# 1010829PA_HVFlyback_GD_Testboard_GDSuppl.net
KiCad netlist of a schematic drawn in Altium Designer
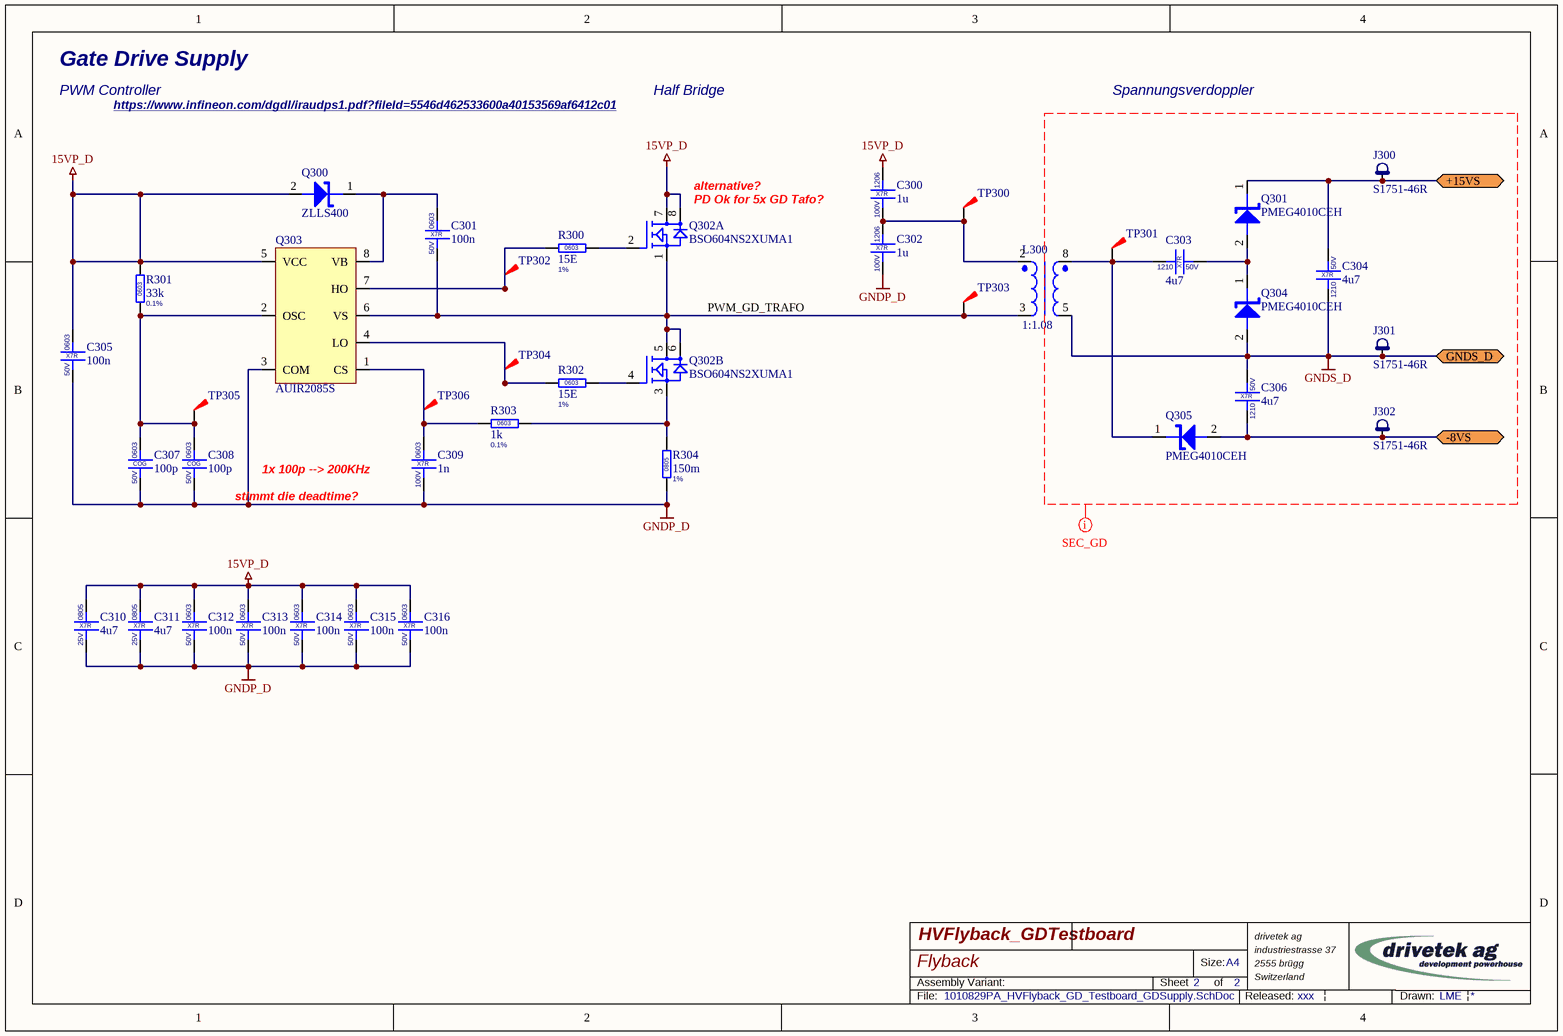
[diagram p0: 1010829PA_HVFlyback_GD_Testboard_GDSupply.SchDoc]

(export (version "E")
  (design (tool "Eeschema 10.0.6"))
  (components
    (comp (ref "C300")
      (value "1u")
      (footprint "02_1206_DRK_3-4x1-8x1-8")
      (fields
        (field (name "CASENAME") "1206")
        (field (name "TYPE3") "X7R")
        (field (name "VOLTAGE") "100V")
        (field (name "PART NUMBER") "02-0297")
        (field (name "TOLERANCE") "10")
        (field (name "AUTHOR") "CSI")
      )
      (libsource (lib "drivetek") (part "02_CAP"))
    )
    (comp (ref "C301")
      (value "100n")
      (footprint "02_0603_DRK_1-7x1-0x0-9")
      (fields
        (field (name "CASENAME") "0603")
        (field (name "TYPE3") "X7R")
        (field (name "VOLTAGE") "50V")
        (field (name "PART NUMBER") "02-0342")
        (field (name "TOLERANCE") "10")
        (field (name "AUTHOR") "RLE")
      )
      (libsource (lib "drivetek") (part "02_CAP"))
    )
    (comp (ref "C302")
      (value "1u")
      (footprint "02_1206_DRK_3-4x1-8x1-8")
      (fields
        (field (name "CASENAME") "1206")
        (field (name "TYPE3") "X7R")
        (field (name "VOLTAGE") "100V")
        (field (name "PART NUMBER") "02-0297")
        (field (name "TOLERANCE") "10")
        (field (name "AUTHOR") "CSI")
      )
      (libsource (lib "drivetek") (part "02_CAP"))
    )
    (comp (ref "C303")
      (value "4u7")
      (footprint "02_1210_DRK_3-2x2-6x2-7")
      (fields
        (field (name "CASENAME") "1210")
        (field (name "TYPE3") "X7R")
        (field (name "VOLTAGE") "50V")
        (field (name "PART NUMBER") "02-0107")
        (field (name "TOLERANCE") "10")
        (field (name "CHECKED") "SBR")
      )
      (libsource (lib "drivetek") (part "02_CAP"))
    )
    (comp (ref "C304")
      (value "4u7")
      (footprint "02_1210_DRK_3-2x2-6x2-7")
      (fields
        (field (name "CASENAME") "1210")
        (field (name "TYPE3") "X7R")
        (field (name "VOLTAGE") "50V")
        (field (name "PART NUMBER") "02-0107")
        (field (name "TOLERANCE") "10")
        (field (name "CHECKED") "SBR")
      )
      (libsource (lib "drivetek") (part "02_CAP"))
    )
    (comp (ref "C305")
      (value "100n")
      (footprint "02_0603_DRK_1-7x1-0x0-9")
      (fields
        (field (name "CASENAME") "0603")
        (field (name "TYPE3") "X7R")
        (field (name "VOLTAGE") "50V")
        (field (name "PART NUMBER") "02-0342")
        (field (name "TOLERANCE") "10")
        (field (name "AUTHOR") "RLE")
      )
      (libsource (lib "drivetek") (part "02_CAP"))
    )
    (comp (ref "C306")
      (value "4u7")
      (footprint "02_1210_DRK_3-2x2-6x2-7")
      (fields
        (field (name "CASENAME") "1210")
        (field (name "TYPE3") "X7R")
        (field (name "VOLTAGE") "50V")
        (field (name "PART NUMBER") "02-0107")
        (field (name "TOLERANCE") "10")
        (field (name "CHECKED") "SBR")
      )
      (libsource (lib "drivetek") (part "02_CAP"))
    )
    (comp (ref "C307")
      (value "100p")
      (footprint "02_0603_DRK_1-7x1-0x0-9")
      (fields
        (field (name "CASENAME") "0603")
        (field (name "TYPE3") "COG")
        (field (name "VOLTAGE") "50V")
        (field (name "PART NUMBER") "02-0380")
        (field (name "TOLERANCE") "5")
        (field (name "AUTHOR") "RLE")
      )
      (libsource (lib "drivetek") (part "02_CAP"))
    )
    (comp (ref "C308")
      (value "100p")
      (footprint "02_0603_DRK_1-7x1-0x0-9")
      (fields
        (field (name "CASENAME") "0603")
        (field (name "TYPE3") "COG")
        (field (name "VOLTAGE") "50V")
        (field (name "PART NUMBER") "02-0380")
        (field (name "TOLERANCE") "5")
        (field (name "AUTHOR") "RLE")
      )
      (libsource (lib "drivetek") (part "02_CAP"))
    )
    (comp (ref "C309")
      (value "1n")
      (footprint "02_0603_DRK_1-7x1-0x0-9")
      (fields
        (field (name "CASENAME") "0603")
        (field (name "TYPE3") "X7R")
        (field (name "VOLTAGE") "100V")
        (field (name "PART NUMBER") "02-0303")
        (field (name "TOLERANCE") "10")
        (field (name "AUTHOR") "RLE")
      )
      (libsource (lib "drivetek") (part "02_CAP"))
    )
    (comp (ref "C310")
      (value "4u7")
      (footprint "02_0805_DRK_2-2x1-5x1-3")
      (fields
        (field (name "CASENAME") "0805")
        (field (name "TYPE3") "X7R")
        (field (name "VOLTAGE") "25V")
        (field (name "PART NUMBER") "02-0268")
        (field (name "TOLERANCE") "10")
        (field (name "AUTHOR") "MFR")
      )
      (libsource (lib "drivetek") (part "02_CAP"))
    )
    (comp (ref "C311")
      (value "4u7")
      (footprint "02_0805_DRK_2-2x1-5x1-3")
      (fields
        (field (name "CASENAME") "0805")
        (field (name "TYPE3") "X7R")
        (field (name "VOLTAGE") "25V")
        (field (name "PART NUMBER") "02-0268")
        (field (name "TOLERANCE") "10")
        (field (name "AUTHOR") "MFR")
      )
      (libsource (lib "drivetek") (part "02_CAP"))
    )
    (comp (ref "C312")
      (value "100n")
      (footprint "02_0603_DRK_1-7x1-0x0-9")
      (fields
        (field (name "CASENAME") "0603")
        (field (name "TYPE3") "X7R")
        (field (name "VOLTAGE") "50V")
        (field (name "PART NUMBER") "02-0342")
        (field (name "TOLERANCE") "10")
        (field (name "AUTHOR") "RLE")
      )
      (libsource (lib "drivetek") (part "02_CAP"))
    )
    (comp (ref "C313")
      (value "100n")
      (footprint "02_0603_DRK_1-7x1-0x0-9")
      (fields
        (field (name "CASENAME") "0603")
        (field (name "TYPE3") "X7R")
        (field (name "VOLTAGE") "50V")
        (field (name "PART NUMBER") "02-0342")
        (field (name "TOLERANCE") "10")
        (field (name "AUTHOR") "RLE")
      )
      (libsource (lib "drivetek") (part "02_CAP"))
    )
    (comp (ref "C314")
      (value "100n")
      (footprint "02_0603_DRK_1-7x1-0x0-9")
      (fields
        (field (name "CASENAME") "0603")
        (field (name "TYPE3") "X7R")
        (field (name "VOLTAGE") "50V")
        (field (name "PART NUMBER") "02-0342")
        (field (name "TOLERANCE") "10")
        (field (name "AUTHOR") "RLE")
      )
      (libsource (lib "drivetek") (part "02_CAP"))
    )
    (comp (ref "C315")
      (value "100n")
      (footprint "02_0603_DRK_1-7x1-0x0-9")
      (fields
        (field (name "CASENAME") "0603")
        (field (name "TYPE3") "X7R")
        (field (name "VOLTAGE") "50V")
        (field (name "PART NUMBER") "02-0342")
        (field (name "TOLERANCE") "10")
        (field (name "AUTHOR") "RLE")
      )
      (libsource (lib "drivetek") (part "02_CAP"))
    )
    (comp (ref "C316")
      (value "100n")
      (footprint "02_0603_DRK_1-7x1-0x0-9")
      (fields
        (field (name "CASENAME") "0603")
        (field (name "TYPE3") "X7R")
        (field (name "VOLTAGE") "50V")
        (field (name "PART NUMBER") "02-0342")
        (field (name "TOLERANCE") "10")
        (field (name "AUTHOR") "RLE")
      )
      (libsource (lib "drivetek") (part "02_CAP"))
    )
    (comp (ref "J300")
      (value "S1751-46R")
      (footprint "13_PAD_DRK_HARWIN_S1751-46")
      (description "Probe Hook")
      (fields (field (name "PART NUMBER") "13-0487") (field (name "AUTHOR") "CSI"))
      (libsource (lib "drivetek") (part "13_ProbeHook"))
    )
    (comp (ref "J301")
      (value "S1751-46R")
      (footprint "13_PAD_DRK_HARWIN_S1751-46")
      (description "Probe Hook")
      (fields (field (name "PART NUMBER") "13-0487") (field (name "AUTHOR") "CSI"))
      (libsource (lib "drivetek") (part "13_ProbeHook"))
    )
    (comp (ref "J302")
      (value "S1751-46R")
      (footprint "13_PAD_DRK_HARWIN_S1751-46")
      (description "Probe Hook")
      (fields (field (name "PART NUMBER") "13-0487") (field (name "AUTHOR") "CSI"))
      (libsource (lib "drivetek") (part "13_ProbeHook"))
    )
    (comp (ref "L300")
      (value "1:1.08")
      (footprint "06_TRA_DRK_TDK-B78307A2276A003")
      (description "Gate Drive Transformer")
      (fields
        (field (name "PART NUMBER") "06-0146")
        (field (name "AUTHOR") "NLE")
        (field (name "COMPONENTLINK1URL") "K:\\Volkswagen\\1779_LE_BZ_Luftversorgung\\03_Hardware\\031_Analyse_Spezifikation\\BS1\\Datenblätter\\Gate Drive Supply\\B78307A2276A003.pdf")
      )
      (libsource (lib "drivetek") (part "06_TRA_DRK_TDK-B78307A2276A003"))
    )
    (comp (ref "Q300")
      (value "ZLLS400")
      (footprint "03_SOD323_DRK")
      (fields
        (field (name "PART NUMBER") "03-0389")
        (field (name "VOLTAGE") "40V")
        (field (name "AUTHOR") "RLE")
        (field (name "CHECKED") "CRA")
      )
      (libsource (lib "drivetek") (part "03_SCHOTTKY_A2-K1"))
    )
    (comp (ref "Q301")
      (value "PMEG4010CEH")
      (footprint "03_SOD123_DRK")
      (fields
        (field (name "PART NUMBER") "03-0124")
        (field (name "VOLTAGE") "40V")
        (field (name "AUTHOR") "MSC")
        (field (name "CHECKED") "HHU")
      )
      (libsource (lib "drivetek") (part "03_SCHOTTKY_A2-K1"))
    )
    (comp (ref "Q302")
      (value "BSO604NS2XUMA1")
      (footprint "03_SO-8_DRK")
      (description "OptiMOS Dual N-Channel 5A 55V 35mOhm, AEC-Q101")
      (fields
        (field (name "PART NUMBER") "03-0419")
        (field (name "VOLTAGE") "55V")
        (field (name "AUTHOR") "RVI")
      )
      (libsource (lib "drivetek") (part "03_NMOS_DUAL_BSO604NS2"))
    )
    (comp (ref "Q303")
      (value "AUIR2085S")
      (footprint "04_SO-8_DRK")
      (description "High Speed Half-Bridge Driver,  Self Oscilating 50%, 1A, 100V, AEC-Q100")
      (fields (field (name "PART NUMBER") "04-0493") (field (name "AUTHOR") "RVI"))
      (libsource (lib "drivetek") (part "04_MIXSIG_AUIR2085S"))
    )
    (comp (ref "Q304")
      (value "PMEG4010CEH")
      (footprint "03_SOD123_DRK")
      (fields
        (field (name "PART NUMBER") "03-0124")
        (field (name "VOLTAGE") "40V")
        (field (name "AUTHOR") "MSC")
        (field (name "CHECKED") "HHU")
      )
      (libsource (lib "drivetek") (part "03_SCHOTTKY_A2-K1"))
    )
    (comp (ref "Q305")
      (value "PMEG4010CEH")
      (footprint "03_SOD123_DRK")
      (fields
        (field (name "PART NUMBER") "03-0124")
        (field (name "VOLTAGE") "40V")
        (field (name "AUTHOR") "MSC")
        (field (name "CHECKED") "HHU")
      )
      (libsource (lib "drivetek") (part "03_SCHOTTKY_A2-K1"))
    )
    (comp (ref "R300")
      (value "15E")
      (footprint "01_0603_DRK_1-7x1-0x0-55")
      (fields
        (field (name "TOLERANCE") "1%")
        (field (name "CASENAME") "0603")
        (field (name "PART NUMBER") "01-0771")
        (field (name "VOLTAGE") "75V")
        (field (name "POWER") "100m")
        (field (name "AUTHOR") "RVI")
      )
      (libsource (lib "drivetek") (part "01_RES"))
    )
    (comp (ref "R301")
      (value "33k")
      (footprint "01_0603_DRK_1-7x1-0x0-55")
      (fields
        (field (name "TOLERANCE") "0.1%")
        (field (name "CASENAME") "0603")
        (field (name "PART NUMBER") "01-0690")
        (field (name "VOLTAGE") "75V")
        (field (name "POWER") "100m")
        (field (name "AUTHOR") "RLE")
      )
      (libsource (lib "drivetek") (part "01_RES"))
    )
    (comp (ref "R302")
      (value "15E")
      (footprint "01_0603_DRK_1-7x1-0x0-55")
      (fields
        (field (name "TOLERANCE") "1%")
        (field (name "CASENAME") "0603")
        (field (name "PART NUMBER") "01-0771")
        (field (name "VOLTAGE") "75V")
        (field (name "POWER") "100m")
        (field (name "AUTHOR") "RVI")
      )
      (libsource (lib "drivetek") (part "01_RES"))
    )
    (comp (ref "R303")
      (value "1k")
      (footprint "01_0603_DRK_1-7x1-0x0-55")
      (fields
        (field (name "TOLERANCE") "0.1%")
        (field (name "CASENAME") "0603")
        (field (name "PART NUMBER") "01-0573")
        (field (name "VOLTAGE") "75V")
        (field (name "POWER") "100m")
        (field (name "AUTHOR") "SSC")
      )
      (libsource (lib "drivetek") (part "01_RES"))
    )
    (comp (ref "R304")
      (value "150m")
      (footprint "01_0805_DRK_2-2x1-5x0-65")
      (fields
        (field (name "TOLERANCE") "1%")
        (field (name "CASENAME") "0805")
        (field (name "PART NUMBER") "01-0781")
        (field (name "POWER") "500m")
        (field (name "AUTHOR") "LME")
      )
      (libsource (lib "drivetek") (part "01_RES"))
    )
    (comp (ref "TP300")
      (value "TP THT Dia 0.8mm, Hole 0.3mm")
      (footprint "13_TP_0-3_0-8mm")
      (fields (field (name "PART NUMBER") "13-0524") (field (name "AUTHOR") "RVI"))
      (libsource (lib "drivetek") (part "13_TESTPOINT"))
    )
    (comp (ref "TP301")
      (value "TP THT Dia 0.8mm, Hole 0.3mm")
      (footprint "13_TP_0-3_0-8mm")
      (fields (field (name "PART NUMBER") "13-0524") (field (name "AUTHOR") "RVI"))
      (libsource (lib "drivetek") (part "13_TESTPOINT"))
    )
    (comp (ref "TP302")
      (value "TP THT Dia 0.8mm, Hole 0.3mm")
      (footprint "13_TP_0-3_0-8mm")
      (fields (field (name "PART NUMBER") "13-0524") (field (name "AUTHOR") "RVI"))
      (libsource (lib "drivetek") (part "13_TESTPOINT"))
    )
    (comp (ref "TP303")
      (value "TP THT Dia 0.8mm, Hole 0.3mm")
      (footprint "13_TP_0-3_0-8mm")
      (fields (field (name "PART NUMBER") "13-0524") (field (name "AUTHOR") "RVI"))
      (libsource (lib "drivetek") (part "13_TESTPOINT"))
    )
    (comp (ref "TP304")
      (value "TP THT Dia 0.8mm, Hole 0.3mm")
      (footprint "13_TP_0-3_0-8mm")
      (fields (field (name "PART NUMBER") "13-0524") (field (name "AUTHOR") "RVI"))
      (libsource (lib "drivetek") (part "13_TESTPOINT"))
    )
    (comp (ref "TP305")
      (value "TP THT Dia 0.8mm, Hole 0.3mm")
      (footprint "13_TP_0-3_0-8mm")
      (fields (field (name "PART NUMBER") "13-0524") (field (name "AUTHOR") "RVI"))
      (libsource (lib "drivetek") (part "13_TESTPOINT"))
    )
    (comp (ref "TP306")
      (value "TP THT Dia 0.8mm, Hole 0.3mm")
      (footprint "13_TP_0-3_0-8mm")
      (fields (field (name "PART NUMBER") "13-0524") (field (name "AUTHOR") "RVI"))
      (libsource (lib "drivetek") (part "13_TESTPOINT"))
    )
  )
  (nets
    (net (code "1") (name "/+15VS") (class "Default")
      (node (ref "C304") (pin "2") (pintype "passive"))
      (node (ref "J300") (pin "1") (pinfunction "1_1") (pintype "passive"))
      (node (ref "Q301") (pin "1") (pintype "passive"))
    )
    (net (code "2") (name "/-8VS") (class "Default")
      (node (ref "C306") (pin "1") (pintype "passive"))
      (node (ref "J302") (pin "1") (pinfunction "1_1") (pintype "passive"))
      (node (ref "Q305") (pin "2") (pintype "passive"))
    )
    (net (code "3") (name "/PWM_GD_TRAFO") (class "Default")
      (node (ref "C301") (pin "2") (pintype "passive"))
      (node (ref "L300") (pin "3") (pinfunction "3_3") (pintype "passive"))
      (node (ref "Q302") (pin "1") (pinfunction "S1_1") (pintype "passive"))
      (node (ref "Q302") (pin "5") (pinfunction "D2_5") (pintype "passive"))
      (node (ref "Q302") (pin "6") (pinfunction "D2_6") (pintype "passive"))
      (node (ref "Q303") (pin "6") (pinfunction "VS_6") (pintype "passive"))
      (node (ref "TP303") (pin "1") (pintype "passive"))
    )
    (net (code "4") (name "15VP_D") (class "Default")
      (node (ref "C300") (pin "1") (pintype "passive"))
      (node (ref "C305") (pin "1") (pintype "passive"))
      (node (ref "C310") (pin "1") (pintype "passive"))
      (node (ref "C311") (pin "1") (pintype "passive"))
      (node (ref "C312") (pin "1") (pintype "passive"))
      (node (ref "C313") (pin "1") (pintype "passive"))
      (node (ref "C314") (pin "1") (pintype "passive"))
      (node (ref "C315") (pin "1") (pintype "passive"))
      (node (ref "C316") (pin "1") (pintype "passive"))
      (node (ref "Q300") (pin "2") (pintype "passive"))
      (node (ref "Q302") (pin "7") (pinfunction "D1_7") (pintype "passive"))
      (node (ref "Q302") (pin "8") (pinfunction "D1_8") (pintype "passive"))
      (node (ref "Q303") (pin "5") (pinfunction "VCC_5") (pintype "passive"))
      (node (ref "R301") (pin "2") (pintype "passive"))
    )
    (net (code "5") (name "GNDP_D") (class "Default")
      (node (ref "C302") (pin "2") (pintype "passive"))
      (node (ref "C305") (pin "2") (pintype "passive"))
      (node (ref "C307") (pin "2") (pintype "passive"))
      (node (ref "C308") (pin "2") (pintype "passive"))
      (node (ref "C309") (pin "2") (pintype "passive"))
      (node (ref "C310") (pin "2") (pintype "passive"))
      (node (ref "C311") (pin "2") (pintype "passive"))
      (node (ref "C312") (pin "2") (pintype "passive"))
      (node (ref "C313") (pin "2") (pintype "passive"))
      (node (ref "C314") (pin "2") (pintype "passive"))
      (node (ref "C315") (pin "2") (pintype "passive"))
      (node (ref "C316") (pin "2") (pintype "passive"))
      (node (ref "Q303") (pin "3") (pinfunction "COM_3") (pintype "passive"))
      (node (ref "R304") (pin "1") (pintype "passive"))
    )
    (net (code "6") (name "GNDS_D") (class "Default")
      (node (ref "C304") (pin "1") (pintype "passive"))
      (node (ref "C306") (pin "2") (pintype "passive"))
      (node (ref "J301") (pin "1") (pinfunction "1_1") (pintype "passive"))
      (node (ref "L300") (pin "5") (pinfunction "5_5") (pintype "passive"))
      (node (ref "Q304") (pin "2") (pintype "passive"))
    )
    (net (code "7") (name "Net-(C300-Pad2)") (class "Default")
      (node (ref "C300") (pin "2") (pintype "passive"))
      (node (ref "C302") (pin "1") (pintype "passive"))
      (node (ref "L300") (pin "2") (pinfunction "2_2") (pintype "passive"))
      (node (ref "TP300") (pin "1") (pintype "passive"))
    )
    (net (code "8") (name "Net-(C303-Pad1)") (class "Default")
      (node (ref "C303") (pin "1") (pintype "passive"))
      (node (ref "L300") (pin "8") (pinfunction "8_8") (pintype "passive"))
      (node (ref "Q305") (pin "1") (pintype "passive"))
      (node (ref "TP301") (pin "1") (pintype "passive"))
    )
    (net (code "9") (name "Net-(C303-Pad2)") (class "Default")
      (node (ref "C303") (pin "2") (pintype "passive"))
      (node (ref "Q301") (pin "2") (pintype "passive"))
      (node (ref "Q304") (pin "1") (pintype "passive"))
    )
    (net (code "10") (name "Net-(Q302A-G1)") (class "Default")
      (node (ref "Q302") (pin "2") (pinfunction "G1_2") (pintype "passive"))
      (node (ref "R300") (pin "2") (pintype "passive"))
    )
    (net (code "11") (name "Net-(Q302B-G2)") (class "Default")
      (node (ref "Q302") (pin "4") (pinfunction "G2_4") (pintype "passive"))
      (node (ref "R302") (pin "2") (pintype "passive"))
    )
    (net (code "12") (name "Net-(Q302B-S2)") (class "Default")
      (node (ref "Q302") (pin "3") (pinfunction "S2_3") (pintype "passive"))
      (node (ref "R303") (pin "1") (pintype "passive"))
      (node (ref "R304") (pin "2") (pintype "passive"))
    )
    (net (code "13") (name "Net-(Q303-CS)") (class "Default")
      (node (ref "C309") (pin "1") (pintype "passive"))
      (node (ref "Q303") (pin "1") (pinfunction "CS_1") (pintype "passive"))
      (node (ref "R303") (pin "2") (pintype "passive"))
      (node (ref "TP306") (pin "1") (pintype "passive"))
    )
    (net (code "14") (name "Net-(Q303-HO)") (class "Default")
      (node (ref "Q303") (pin "7") (pinfunction "HO_7") (pintype "passive"))
      (node (ref "R300") (pin "1") (pintype "passive"))
      (node (ref "TP302") (pin "1") (pintype "passive"))
    )
    (net (code "15") (name "Net-(Q303-LO)") (class "Default")
      (node (ref "Q303") (pin "4") (pinfunction "LO_4") (pintype "power_in"))
      (node (ref "R302") (pin "1") (pintype "passive"))
      (node (ref "TP304") (pin "1") (pintype "passive"))
    )
    (net (code "16") (name "Net-(Q303-OSC)") (class "Default")
      (node (ref "C307") (pin "1") (pintype "passive"))
      (node (ref "C308") (pin "1") (pintype "passive"))
      (node (ref "Q303") (pin "2") (pinfunction "OSC_2") (pintype "passive"))
      (node (ref "R301") (pin "1") (pintype "passive"))
      (node (ref "TP305") (pin "1") (pintype "passive"))
    )
    (net (code "17") (name "Net-(Q303-VB)") (class "Default")
      (node (ref "C301") (pin "1") (pintype "passive"))
      (node (ref "Q300") (pin "1") (pintype "passive"))
      (node (ref "Q303") (pin "8") (pinfunction "VB_8") (pintype "power_in"))
    )
  )
)
